# fedordesk.net
KiCad netlist of a schematic drawn in EAGLE
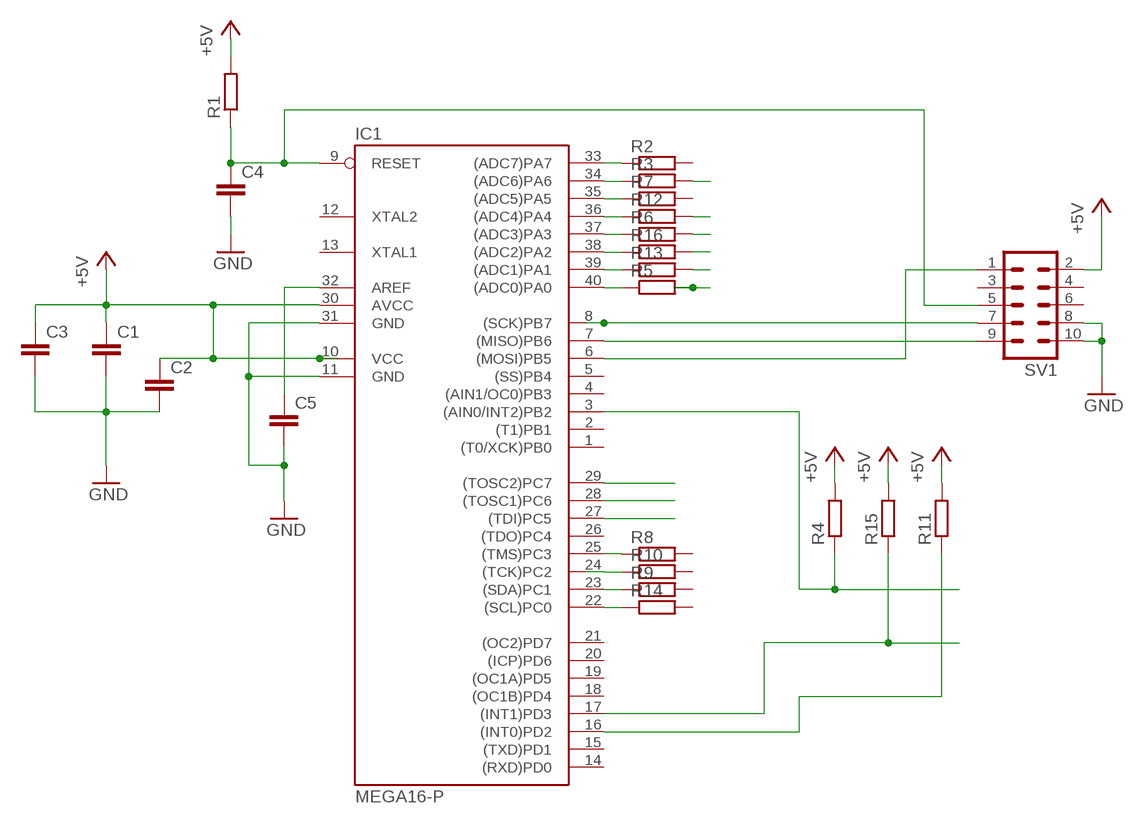
[diagram p0: schematic, sheet 1]

(export (version "E")
  (design (tool "Eeschema 10.0.6"))
  (components
    (comp (ref "C1")
      (value "C-EU050-024X044")
      (footprint "eagle-import:C050-024X044")
      (libsource (lib "eagle-import") (part "C-EU050-024X044"))
    )
    (comp (ref "C2")
      (value "C-EU050-024X044")
      (footprint "eagle-import:C050-024X044")
      (libsource (lib "eagle-import") (part "C-EU050-024X044"))
    )
    (comp (ref "C3")
      (value "C-EU050-024X044")
      (footprint "eagle-import:C050-024X044")
      (libsource (lib "eagle-import") (part "C-EU050-024X044"))
    )
    (comp (ref "C4")
      (value "C-EU050-024X044")
      (footprint "eagle-import:C050-024X044")
      (libsource (lib "eagle-import") (part "C-EU050-024X044"))
    )
    (comp (ref "C5")
      (value "C-EU050-024X044")
      (footprint "eagle-import:C050-024X044")
      (libsource (lib "eagle-import") (part "C-EU050-024X044"))
    )
    (comp (ref "IC1")
      (value "MEGA16-P")
      (footprint "eagle-import:DIL40")
      (fields (field (name "MPN") "ATMEGA16-16PU"))
      (libsource (lib "eagle-import") (part "MEGA16-P"))
    )
    (comp (ref "R1")
      (value "R-EU_0207/10")
      (footprint "eagle-import:0207_10")
      (libsource (lib "eagle-import") (part "R-EU_0207/10"))
    )
    (comp (ref "R2")
      (value "R-EU_0207/10")
      (footprint "eagle-import:0207_10")
      (libsource (lib "eagle-import") (part "R-EU_0207/10"))
    )
    (comp (ref "R3")
      (value "R-EU_0207/10")
      (footprint "eagle-import:0207_10")
      (libsource (lib "eagle-import") (part "R-EU_0207/10"))
    )
    (comp (ref "R4")
      (value "R-EU_0207/10")
      (footprint "eagle-import:0207_10")
      (libsource (lib "eagle-import") (part "R-EU_0207/10"))
    )
    (comp (ref "R5")
      (value "R-EU_0207/10")
      (footprint "eagle-import:0207_10")
      (libsource (lib "eagle-import") (part "R-EU_0207/10"))
    )
    (comp (ref "R6")
      (value "R-EU_0207/10")
      (footprint "eagle-import:0207_10")
      (libsource (lib "eagle-import") (part "R-EU_0207/10"))
    )
    (comp (ref "R7")
      (value "R-EU_0207/10")
      (footprint "eagle-import:0207_10")
      (libsource (lib "eagle-import") (part "R-EU_0207/10"))
    )
    (comp (ref "R8")
      (value "R-EU_0207/10")
      (footprint "eagle-import:0207_10")
      (libsource (lib "eagle-import") (part "R-EU_0207/10"))
    )
    (comp (ref "R9")
      (value "R-EU_0207/10")
      (footprint "eagle-import:0207_10")
      (libsource (lib "eagle-import") (part "R-EU_0207/10"))
    )
    (comp (ref "R10")
      (value "R-EU_0207/10")
      (footprint "eagle-import:0207_10")
      (libsource (lib "eagle-import") (part "R-EU_0207/10"))
    )
    (comp (ref "R11")
      (value "R-EU_0207/10")
      (footprint "eagle-import:0207_10")
      (libsource (lib "eagle-import") (part "R-EU_0207/10"))
    )
    (comp (ref "R12")
      (value "R-EU_0207/10")
      (footprint "eagle-import:0207_10")
      (libsource (lib "eagle-import") (part "R-EU_0207/10"))
    )
    (comp (ref "R13")
      (value "R-EU_0207/10")
      (footprint "eagle-import:0207_10")
      (libsource (lib "eagle-import") (part "R-EU_0207/10"))
    )
    (comp (ref "R14")
      (value "R-EU_0207/10")
      (footprint "eagle-import:0207_10")
      (libsource (lib "eagle-import") (part "R-EU_0207/10"))
    )
    (comp (ref "R15")
      (value "R-EU_0207/10")
      (footprint "eagle-import:0207_10")
      (libsource (lib "eagle-import") (part "R-EU_0207/10"))
    )
    (comp (ref "R16")
      (value "R-EU_0207/10")
      (footprint "eagle-import:0207_10")
      (libsource (lib "eagle-import") (part "R-EU_0207/10"))
    )
    (comp (ref "SV1")
      (value "ML10L")
      (footprint "eagle-import:ML10L")
      (libsource (lib "eagle-import") (part "ML10L"))
    )
  )
  (nets
    (net (code "1") (name "+5V") (class "Default")
      (node (ref "C1") (pin "1") (pinfunction "1_1") (pintype "passive"))
      (node (ref "C2") (pin "1") (pinfunction "1_1") (pintype "passive"))
      (node (ref "C3") (pin "1") (pinfunction "1_1") (pintype "passive"))
      (node (ref "IC1") (pin "10") (pinfunction "VCC_10") (pintype "power_in"))
      (node (ref "IC1") (pin "30") (pinfunction "AVCC_30") (pintype "power_in"))
      (node (ref "R1") (pin "2") (pinfunction "2_2") (pintype "passive"))
      (node (ref "R11") (pin "2") (pinfunction "2_2") (pintype "passive"))
      (node (ref "R15") (pin "2") (pinfunction "2_2") (pintype "passive"))
      (node (ref "R4") (pin "2") (pinfunction "2_2") (pintype "passive"))
      (node (ref "SV1") (pin "2") (pinfunction "2_2") (pintype "passive"))
    )
    (net (code "2") (name "GND") (class "Default")
      (node (ref "C1") (pin "2") (pinfunction "2_2") (pintype "passive"))
      (node (ref "C2") (pin "2") (pinfunction "2_2") (pintype "passive"))
      (node (ref "C3") (pin "2") (pinfunction "2_2") (pintype "passive"))
      (node (ref "C4") (pin "2") (pinfunction "2_2") (pintype "passive"))
      (node (ref "C5") (pin "2") (pinfunction "2_2") (pintype "passive"))
      (node (ref "IC1") (pin "11") (pinfunction "GND_11") (pintype "power_in"))
      (node (ref "IC1") (pin "31") (pinfunction "GND_31") (pintype "power_in"))
      (node (ref "SV1") (pin "10") (pinfunction "10_10") (pintype "passive"))
      (node (ref "SV1") (pin "8") (pinfunction "8_8") (pintype "passive"))
    )
    (net (code "3") (name "Net-(IC1-(ADC0)PA0)") (class "Default")
      (node (ref "IC1") (pin "40") (pinfunction "(ADC0)PA0_40") (pintype "bidirectional"))
      (node (ref "R5") (pin "1") (pinfunction "1_1") (pintype "passive"))
    )
    (net (code "4") (name "Net-(IC1-(ADC1)PA1)") (class "Default")
      (node (ref "IC1") (pin "39") (pinfunction "(ADC1)PA1_39") (pintype "bidirectional"))
      (node (ref "R13") (pin "1") (pinfunction "1_1") (pintype "passive"))
    )
    (net (code "5") (name "Net-(IC1-(ADC2)PA2)") (class "Default")
      (node (ref "IC1") (pin "38") (pinfunction "(ADC2)PA2_38") (pintype "bidirectional"))
      (node (ref "R16") (pin "1") (pinfunction "1_1") (pintype "passive"))
    )
    (net (code "6") (name "Net-(IC1-(ADC3)PA3)") (class "Default")
      (node (ref "IC1") (pin "37") (pinfunction "(ADC3)PA3_37") (pintype "bidirectional"))
      (node (ref "R6") (pin "1") (pinfunction "1_1") (pintype "passive"))
    )
    (net (code "7") (name "Net-(IC1-(ADC4)PA4)") (class "Default")
      (node (ref "IC1") (pin "36") (pinfunction "(ADC4)PA4_36") (pintype "bidirectional"))
      (node (ref "R12") (pin "1") (pinfunction "1_1") (pintype "passive"))
    )
    (net (code "8") (name "Net-(IC1-(ADC5)PA5)") (class "Default")
      (node (ref "IC1") (pin "35") (pinfunction "(ADC5)PA5_35") (pintype "bidirectional"))
      (node (ref "R7") (pin "1") (pinfunction "1_1") (pintype "passive"))
    )
    (net (code "9") (name "Net-(IC1-(ADC6)PA6)") (class "Default")
      (node (ref "IC1") (pin "34") (pinfunction "(ADC6)PA6_34") (pintype "bidirectional"))
      (node (ref "R3") (pin "1") (pinfunction "1_1") (pintype "passive"))
    )
    (net (code "10") (name "Net-(IC1-(ADC7)PA7)") (class "Default")
      (node (ref "IC1") (pin "33") (pinfunction "(ADC7)PA7_33") (pintype "bidirectional"))
      (node (ref "R2") (pin "1") (pinfunction "1_1") (pintype "passive"))
    )
    (net (code "11") (name "Net-(IC1-(AIN0{slash}INT2)PB2)") (class "Default")
      (node (ref "IC1") (pin "3") (pinfunction "(AIN0/INT2)PB2_3") (pintype "bidirectional"))
      (node (ref "R4") (pin "1") (pinfunction "1_1") (pintype "passive"))
    )
    (net (code "12") (name "Net-(IC1-(INT0)PD2)") (class "Default")
      (node (ref "IC1") (pin "16") (pinfunction "(INT0)PD2_16") (pintype "bidirectional"))
      (node (ref "R11") (pin "1") (pinfunction "1_1") (pintype "passive"))
    )
    (net (code "13") (name "Net-(IC1-(INT1)PD3)") (class "Default")
      (node (ref "IC1") (pin "17") (pinfunction "(INT1)PD3_17") (pintype "bidirectional"))
      (node (ref "R15") (pin "1") (pinfunction "1_1") (pintype "passive"))
    )
    (net (code "14") (name "Net-(IC1-(MISO)PB6)") (class "Default")
      (node (ref "IC1") (pin "7") (pinfunction "(MISO)PB6_7") (pintype "bidirectional"))
      (node (ref "SV1") (pin "9") (pinfunction "9_9") (pintype "passive"))
    )
    (net (code "15") (name "Net-(IC1-(MOSI)PB5)") (class "Default")
      (node (ref "IC1") (pin "6") (pinfunction "(MOSI)PB5_6") (pintype "bidirectional"))
      (node (ref "SV1") (pin "1") (pinfunction "1_1") (pintype "passive"))
    )
    (net (code "16") (name "Net-(IC1-(SCK)PB7)") (class "Default")
      (node (ref "IC1") (pin "8") (pinfunction "(SCK)PB7_8") (pintype "bidirectional"))
      (node (ref "SV1") (pin "7") (pinfunction "7_7") (pintype "passive"))
    )
    (net (code "17") (name "Net-(IC1-(SCL)PC0)") (class "Default")
      (node (ref "IC1") (pin "22") (pinfunction "(SCL)PC0_22") (pintype "bidirectional"))
      (node (ref "R14") (pin "1") (pinfunction "1_1") (pintype "passive"))
    )
    (net (code "18") (name "Net-(IC1-(SDA)PC1)") (class "Default")
      (node (ref "IC1") (pin "23") (pinfunction "(SDA)PC1_23") (pintype "bidirectional"))
      (node (ref "R9") (pin "1") (pinfunction "1_1") (pintype "passive"))
    )
    (net (code "19") (name "Net-(IC1-(TCK)PC2)") (class "Default")
      (node (ref "IC1") (pin "24") (pinfunction "(TCK)PC2_24") (pintype "bidirectional"))
      (node (ref "R10") (pin "1") (pinfunction "1_1") (pintype "passive"))
    )
    (net (code "20") (name "Net-(IC1-(TMS)PC3)") (class "Default")
      (node (ref "IC1") (pin "25") (pinfunction "(TMS)PC3_25") (pintype "bidirectional"))
      (node (ref "R8") (pin "1") (pinfunction "1_1") (pintype "passive"))
    )
    (net (code "21") (name "Net-(IC1-AREF)") (class "Default")
      (node (ref "C5") (pin "1") (pinfunction "1_1") (pintype "passive"))
      (node (ref "IC1") (pin "32") (pinfunction "AREF_32") (pintype "passive"))
    )
    (net (code "22") (name "Net-(IC1-RESET)") (class "Default")
      (node (ref "C4") (pin "1") (pinfunction "1_1") (pintype "passive"))
      (node (ref "IC1") (pin "9") (pinfunction "RESET_9") (pintype "input"))
      (node (ref "R1") (pin "1") (pinfunction "1_1") (pintype "passive"))
      (node (ref "SV1") (pin "5") (pinfunction "5_5") (pintype "passive"))
    )
    (net (code "23") (name "unconnected-(IC1-(AIN1{slash}OC0)PB3-Pad4)") (class "Default")
      (node (ref "IC1") (pin "4") (pinfunction "(AIN1/OC0)PB3_4") (pintype "bidirectional"))
    )
    (net (code "24") (name "unconnected-(IC1-(ICP)PD6-Pad20)") (class "Default")
      (node (ref "IC1") (pin "20") (pinfunction "(ICP)PD6_20") (pintype "bidirectional"))
    )
    (net (code "25") (name "unconnected-(IC1-(OC1A)PD5-Pad19)") (class "Default")
      (node (ref "IC1") (pin "19") (pinfunction "(OC1A)PD5_19") (pintype "bidirectional"))
    )
    (net (code "26") (name "unconnected-(IC1-(OC1B)PD4-Pad18)") (class "Default")
      (node (ref "IC1") (pin "18") (pinfunction "(OC1B)PD4_18") (pintype "bidirectional"))
    )
    (net (code "27") (name "unconnected-(IC1-(OC2)PD7-Pad21)") (class "Default")
      (node (ref "IC1") (pin "21") (pinfunction "(OC2)PD7_21") (pintype "bidirectional"))
    )
    (net (code "28") (name "unconnected-(IC1-(RXD)PD0-Pad14)") (class "Default")
      (node (ref "IC1") (pin "14") (pinfunction "(RXD)PD0_14") (pintype "bidirectional"))
    )
    (net (code "29") (name "unconnected-(IC1-(SS)PB4-Pad5)") (class "Default")
      (node (ref "IC1") (pin "5") (pinfunction "(SS)PB4_5") (pintype "bidirectional"))
    )
    (net (code "30") (name "unconnected-(IC1-(T0{slash}XCK)PB0-Pad1)") (class "Default")
      (node (ref "IC1") (pin "1") (pinfunction "(T0/XCK)PB0_1") (pintype "bidirectional"))
    )
    (net (code "31") (name "unconnected-(IC1-(T1)PB1-Pad2)") (class "Default")
      (node (ref "IC1") (pin "2") (pinfunction "(T1)PB1_2") (pintype "bidirectional"))
    )
    (net (code "32") (name "unconnected-(IC1-(TDI)PC5-Pad27)") (class "Default")
      (node (ref "IC1") (pin "27") (pinfunction "(TDI)PC5_27") (pintype "bidirectional"))
    )
    (net (code "33") (name "unconnected-(IC1-(TDO)PC4-Pad26)") (class "Default")
      (node (ref "IC1") (pin "26") (pinfunction "(TDO)PC4_26") (pintype "bidirectional"))
    )
    (net (code "34") (name "unconnected-(IC1-(TOSC1)PC6-Pad28)") (class "Default")
      (node (ref "IC1") (pin "28") (pinfunction "(TOSC1)PC6_28") (pintype "bidirectional"))
    )
    (net (code "35") (name "unconnected-(IC1-(TOSC2)PC7-Pad29)") (class "Default")
      (node (ref "IC1") (pin "29") (pinfunction "(TOSC2)PC7_29") (pintype "bidirectional"))
    )
    (net (code "36") (name "unconnected-(IC1-(TXD)PD1-Pad15)") (class "Default")
      (node (ref "IC1") (pin "15") (pinfunction "(TXD)PD1_15") (pintype "bidirectional"))
    )
    (net (code "37") (name "unconnected-(IC1-XTAL1-Pad13)") (class "Default")
      (node (ref "IC1") (pin "13") (pinfunction "XTAL1_13") (pintype "bidirectional"))
    )
    (net (code "38") (name "unconnected-(IC1-XTAL2-Pad12)") (class "Default")
      (node (ref "IC1") (pin "12") (pinfunction "XTAL2_12") (pintype "bidirectional"))
    )
    (net (code "39") (name "unconnected-(R2-Pad2)") (class "Default")
      (node (ref "R2") (pin "2") (pinfunction "2_2") (pintype "passive"))
    )
    (net (code "40") (name "unconnected-(R3-Pad2)") (class "Default")
      (node (ref "R3") (pin "2") (pinfunction "2_2") (pintype "passive"))
    )
    (net (code "41") (name "unconnected-(R5-Pad2)") (class "Default")
      (node (ref "R5") (pin "2") (pinfunction "2_2") (pintype "passive"))
    )
    (net (code "42") (name "unconnected-(R6-Pad2)") (class "Default")
      (node (ref "R6") (pin "2") (pinfunction "2_2") (pintype "passive"))
    )
    (net (code "43") (name "unconnected-(R7-Pad2)") (class "Default")
      (node (ref "R7") (pin "2") (pinfunction "2_2") (pintype "passive"))
    )
    (net (code "44") (name "unconnected-(R8-Pad2)") (class "Default")
      (node (ref "R8") (pin "2") (pinfunction "2_2") (pintype "passive"))
    )
    (net (code "45") (name "unconnected-(R9-Pad2)") (class "Default")
      (node (ref "R9") (pin "2") (pinfunction "2_2") (pintype "passive"))
    )
    (net (code "46") (name "unconnected-(R10-Pad2)") (class "Default")
      (node (ref "R10") (pin "2") (pinfunction "2_2") (pintype "passive"))
    )
    (net (code "47") (name "unconnected-(R12-Pad2)") (class "Default")
      (node (ref "R12") (pin "2") (pinfunction "2_2") (pintype "passive"))
    )
    (net (code "48") (name "unconnected-(R13-Pad2)") (class "Default")
      (node (ref "R13") (pin "2") (pinfunction "2_2") (pintype "passive"))
    )
    (net (code "49") (name "unconnected-(R14-Pad2)") (class "Default")
      (node (ref "R14") (pin "2") (pinfunction "2_2") (pintype "passive"))
    )
    (net (code "50") (name "unconnected-(R16-Pad2)") (class "Default")
      (node (ref "R16") (pin "2") (pinfunction "2_2") (pintype "passive"))
    )
    (net (code "51") (name "unconnected-(SV1-Pad3)") (class "Default")
      (node (ref "SV1") (pin "3") (pinfunction "3_3") (pintype "passive"))
    )
    (net (code "52") (name "unconnected-(SV1-Pad4)") (class "Default")
      (node (ref "SV1") (pin "4") (pinfunction "4_4") (pintype "passive"))
    )
    (net (code "53") (name "unconnected-(SV1-Pad6)") (class "Default")
      (node (ref "SV1") (pin "6") (pinfunction "6_6") (pintype "passive"))
    )
  )
)
